# powersensor.net
KiCad netlist of a schematic drawn in EAGLE
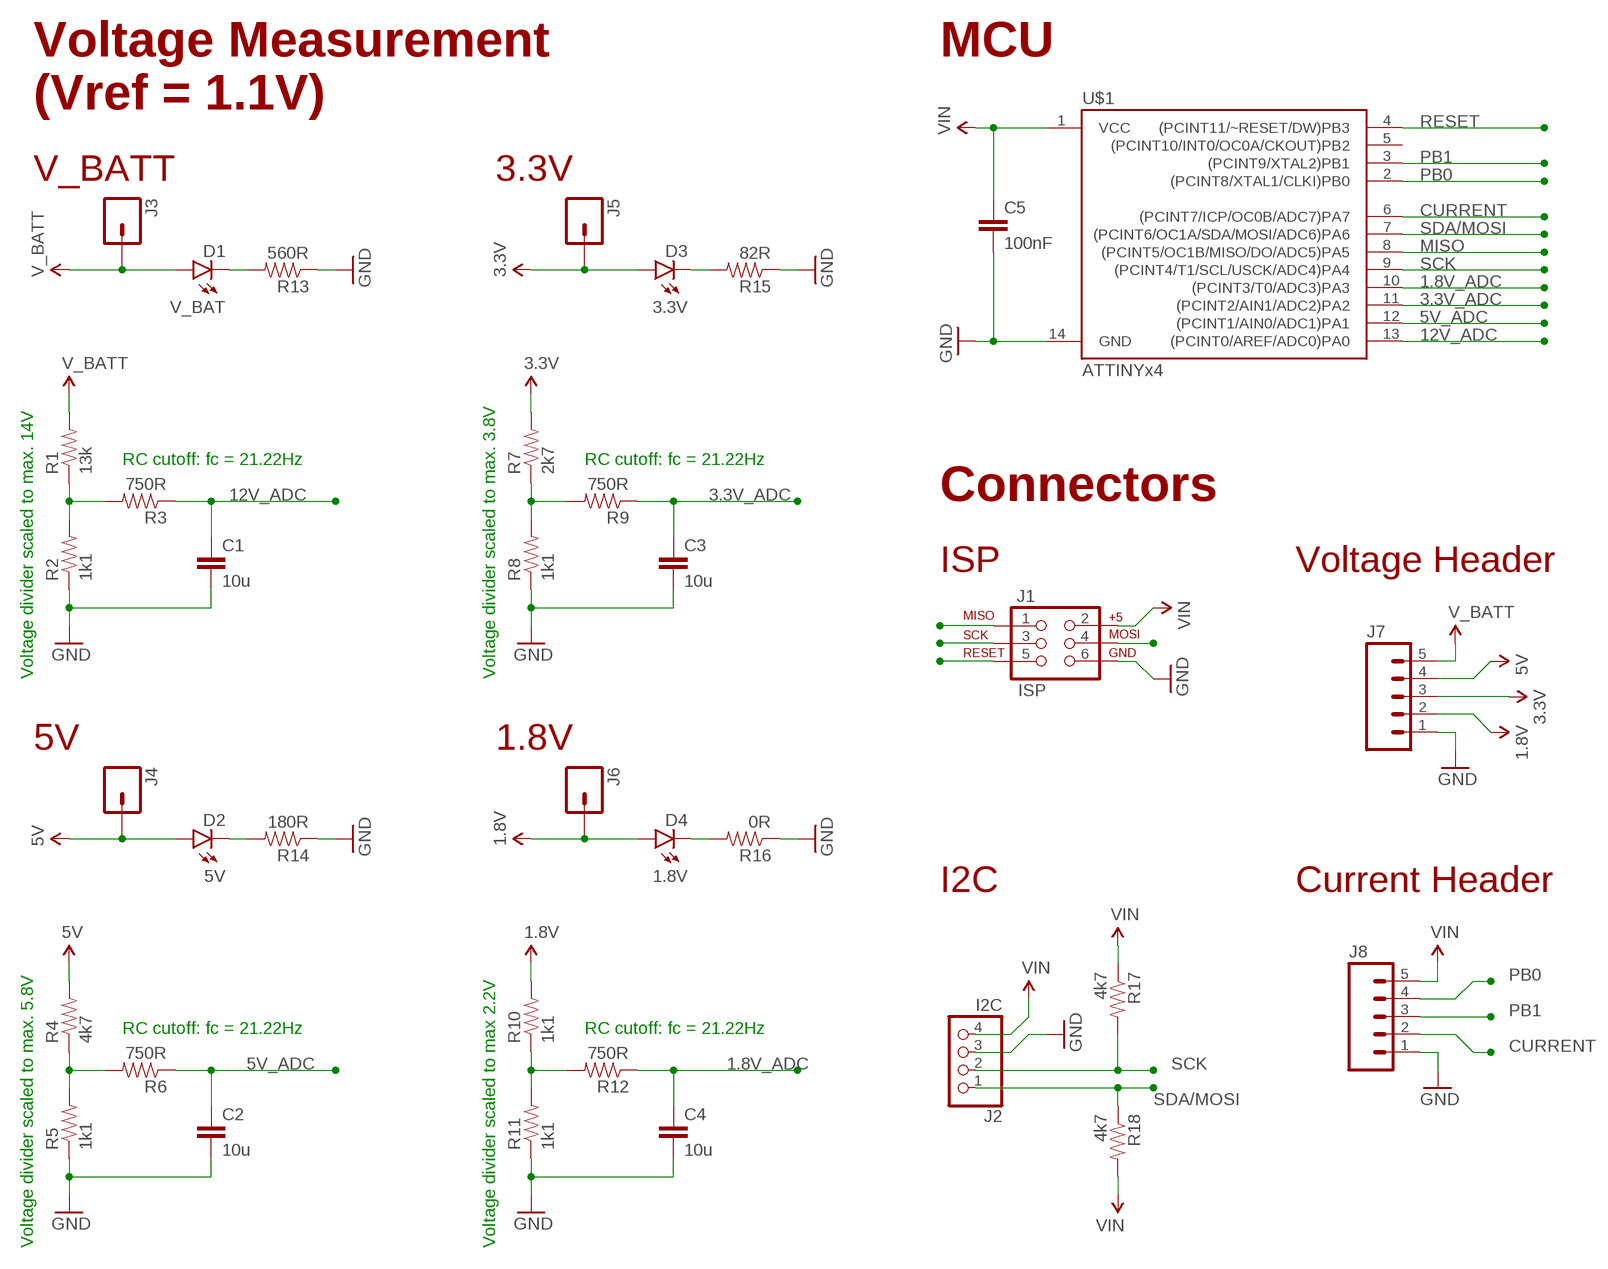
[diagram p0: schematic, sheet 1]

(export (version "E")
  (design (tool "Eeschema 10.0.6"))
  (components
    (comp (ref "C1")
      (value "10u")
      (footprint "eagle-import:0603-CAP")
      (libsource (lib "eagle-import") (part "CAP0603-CAP"))
    )
    (comp (ref "C2")
      (value "10u")
      (footprint "eagle-import:0603-CAP")
      (libsource (lib "eagle-import") (part "CAP0603-CAP"))
    )
    (comp (ref "C3")
      (value "10u")
      (footprint "eagle-import:0603-CAP")
      (libsource (lib "eagle-import") (part "CAP0603-CAP"))
    )
    (comp (ref "C4")
      (value "10u")
      (footprint "eagle-import:0603-CAP")
      (libsource (lib "eagle-import") (part "CAP0603-CAP"))
    )
    (comp (ref "C5")
      (value "100nF")
      (footprint "eagle-import:0603-CAP")
      (libsource (lib "eagle-import") (part "CAP0603-CAP"))
    )
    (comp (ref "D1")
      (value "V_BAT")
      (footprint "eagle-import:LED-0603")
      (libsource (lib "eagle-import") (part "LED0603"))
    )
    (comp (ref "D2")
      (value "5V")
      (footprint "eagle-import:LED-0603")
      (libsource (lib "eagle-import") (part "LED0603"))
    )
    (comp (ref "D3")
      (value "3.3V")
      (footprint "eagle-import:LED-0603")
      (libsource (lib "eagle-import") (part "LED0603"))
    )
    (comp (ref "D4")
      (value "1.8V")
      (footprint "eagle-import:LED-0603")
      (libsource (lib "eagle-import") (part "LED0603"))
    )
    (comp (ref "J1")
      (value "ISP")
      (footprint "eagle-import:2X3")
      (libsource (lib "eagle-import") (part "AVR_SPI_PRG_6PTH"))
    )
    (comp (ref "J2")
      (value "I2C")
      (footprint "eagle-import:1X04_90")
      (libsource (lib "eagle-import") (part "PINHD-1X4/90"))
    )
    (comp (ref "J3")
      (value "M01PTH")
      (footprint "eagle-import:1X01")
      (libsource (lib "eagle-import") (part "M01PTH"))
    )
    (comp (ref "J4")
      (value "M01PTH")
      (footprint "eagle-import:1X01")
      (libsource (lib "eagle-import") (part "M01PTH"))
    )
    (comp (ref "J5")
      (value "M01PTH")
      (footprint "eagle-import:1X01")
      (libsource (lib "eagle-import") (part "M01PTH"))
    )
    (comp (ref "J6")
      (value "M01PTH")
      (footprint "eagle-import:1X01")
      (libsource (lib "eagle-import") (part "M01PTH"))
    )
    (comp (ref "J7")
      (value "M05PTH")
      (footprint "eagle-import:1X05")
      (libsource (lib "eagle-import") (part "M05PTH"))
    )
    (comp (ref "J8")
      (value "M05PTH")
      (footprint "eagle-import:1X05")
      (libsource (lib "eagle-import") (part "M05PTH"))
    )
    (comp (ref "R1")
      (value "13k")
      (footprint "eagle-import:0603-RES")
      (libsource (lib "eagle-import") (part "RESISTOR0603-RES"))
    )
    (comp (ref "R2")
      (value "1k1")
      (footprint "eagle-import:0603-RES")
      (libsource (lib "eagle-import") (part "RESISTOR0603-RES"))
    )
    (comp (ref "R3")
      (value "750R")
      (footprint "eagle-import:0603-RES")
      (libsource (lib "eagle-import") (part "RESISTOR0603-RES"))
    )
    (comp (ref "R4")
      (value "4k7")
      (footprint "eagle-import:0603-RES")
      (libsource (lib "eagle-import") (part "RESISTOR0603-RES"))
    )
    (comp (ref "R5")
      (value "1k1")
      (footprint "eagle-import:0603-RES")
      (libsource (lib "eagle-import") (part "RESISTOR0603-RES"))
    )
    (comp (ref "R6")
      (value "750R")
      (footprint "eagle-import:0603-RES")
      (libsource (lib "eagle-import") (part "RESISTOR0603-RES"))
    )
    (comp (ref "R7")
      (value "2k7")
      (footprint "eagle-import:0603-RES")
      (libsource (lib "eagle-import") (part "RESISTOR0603-RES"))
    )
    (comp (ref "R8")
      (value "1k1")
      (footprint "eagle-import:0603-RES")
      (libsource (lib "eagle-import") (part "RESISTOR0603-RES"))
    )
    (comp (ref "R9")
      (value "750R")
      (footprint "eagle-import:0603-RES")
      (libsource (lib "eagle-import") (part "RESISTOR0603-RES"))
    )
    (comp (ref "R10")
      (value "1k1")
      (footprint "eagle-import:0603-RES")
      (libsource (lib "eagle-import") (part "RESISTOR0603-RES"))
    )
    (comp (ref "R11")
      (value "1k1")
      (footprint "eagle-import:0603-RES")
      (libsource (lib "eagle-import") (part "RESISTOR0603-RES"))
    )
    (comp (ref "R12")
      (value "750R")
      (footprint "eagle-import:0603-RES")
      (libsource (lib "eagle-import") (part "RESISTOR0603-RES"))
    )
    (comp (ref "R13")
      (value "560R")
      (footprint "eagle-import:0603-RES")
      (libsource (lib "eagle-import") (part "RESISTOR0603-RES"))
    )
    (comp (ref "R14")
      (value "180R")
      (footprint "eagle-import:0603-RES")
      (libsource (lib "eagle-import") (part "RESISTOR0603-RES"))
    )
    (comp (ref "R15")
      (value "82R")
      (footprint "eagle-import:0603-RES")
      (libsource (lib "eagle-import") (part "RESISTOR0603-RES"))
    )
    (comp (ref "R16")
      (value "0R")
      (footprint "eagle-import:0603-RES")
      (libsource (lib "eagle-import") (part "RESISTOR0603-RES"))
    )
    (comp (ref "R17")
      (value "4k7")
      (footprint "eagle-import:0603-RES")
      (libsource (lib "eagle-import") (part "RESISTOR0603-RES"))
    )
    (comp (ref "R18")
      (value "4k7")
      (footprint "eagle-import:0603-RES")
      (libsource (lib "eagle-import") (part "RESISTOR0603-RES"))
    )
    (comp (ref "U$1")
      (value "ATTINYx4")
      (footprint "eagle-import:SO14")
      (libsource (lib "eagle-import") (part "ATTINY84"))
    )
  )
  (nets
    (net (code "1") (name "/1.8V_ADC") (class "Default")
      (node (ref "C4") (pin "1") (pinfunction "1_1") (pintype "passive"))
      (node (ref "R12") (pin "1") (pinfunction "1_1") (pintype "passive"))
      (node (ref "U$1") (pin "10") (pinfunction "(PCINT3/T0/ADC3)PA3_10") (pintype "bidirectional"))
    )
    (net (code "2") (name "/3.3V_ADC") (class "Default")
      (node (ref "C3") (pin "1") (pinfunction "1_1") (pintype "passive"))
      (node (ref "R9") (pin "1") (pinfunction "1_1") (pintype "passive"))
      (node (ref "U$1") (pin "11") (pinfunction "(PCINT2/AIN1/ADC2)PA2_11") (pintype "bidirectional"))
    )
    (net (code "3") (name "/5V_ADC") (class "Default")
      (node (ref "C2") (pin "1") (pinfunction "1_1") (pintype "passive"))
      (node (ref "R6") (pin "1") (pinfunction "1_1") (pintype "passive"))
      (node (ref "U$1") (pin "12") (pinfunction "(PCINT1/AIN0/ADC1)PA1_12") (pintype "bidirectional"))
    )
    (net (code "4") (name "/12V_ADC") (class "Default")
      (node (ref "C1") (pin "1") (pinfunction "1_1") (pintype "passive"))
      (node (ref "R3") (pin "1") (pinfunction "1_1") (pintype "passive"))
      (node (ref "U$1") (pin "13") (pinfunction "(PCINT0/AREF/ADC0)PA0_13") (pintype "bidirectional"))
    )
    (net (code "5") (name "/CURRENT") (class "Default")
      (node (ref "J8") (pin "2") (pinfunction "2_2") (pintype "passive"))
      (node (ref "U$1") (pin "6") (pinfunction "(PCINT7/ICP/OC0B/ADC7)PA7_6") (pintype "bidirectional"))
    )
    (net (code "6") (name "/MISO") (class "Default")
      (node (ref "J1") (pin "1") (pinfunction "1_1") (pintype "passive"))
      (node (ref "U$1") (pin "8") (pinfunction "(PCINT5/OC1B/MISO/DO/ADC5)PA5_8") (pintype "bidirectional"))
    )
    (net (code "7") (name "/PB0") (class "Default")
      (node (ref "J8") (pin "4") (pinfunction "4_4") (pintype "passive"))
      (node (ref "U$1") (pin "2") (pinfunction "(PCINT8/XTAL1/CLKI)PB0_2") (pintype "bidirectional"))
    )
    (net (code "8") (name "/PB1") (class "Default")
      (node (ref "J8") (pin "3") (pinfunction "3_3") (pintype "passive"))
      (node (ref "U$1") (pin "3") (pinfunction "(PCINT9/XTAL2)PB1_3") (pintype "bidirectional"))
    )
    (net (code "9") (name "/RESET") (class "Default")
      (node (ref "J1") (pin "5") (pinfunction "5_5") (pintype "passive"))
      (node (ref "U$1") (pin "4") (pinfunction "(PCINT11/~{RESET/DW})PB3_4") (pintype "bidirectional"))
    )
    (net (code "10") (name "/SCK") (class "Default")
      (node (ref "J1") (pin "3") (pinfunction "3_3") (pintype "passive"))
      (node (ref "J2") (pin "2") (pinfunction "2_2") (pintype "passive"))
      (node (ref "R17") (pin "2") (pinfunction "2_2") (pintype "passive"))
      (node (ref "U$1") (pin "9") (pinfunction "(PCINT4/T1/SCL/USCK/ADC4)PA4_9") (pintype "bidirectional"))
    )
    (net (code "11") (name "/SDA{slash}MOSI") (class "Default")
      (node (ref "J1") (pin "4") (pinfunction "4_4") (pintype "passive"))
      (node (ref "J2") (pin "1") (pinfunction "1_1") (pintype "passive"))
      (node (ref "R18") (pin "1") (pinfunction "1_1") (pintype "passive"))
      (node (ref "U$1") (pin "7") (pinfunction "(PCINT6/OC1A/SDA/MOSI/ADC6)PA6_7") (pintype "bidirectional"))
    )
    (net (code "12") (name "1.8V") (class "Default")
      (node (ref "D4") (pin "A") (pinfunction "A_A") (pintype "passive"))
      (node (ref "J6") (pin "1") (pinfunction "1_1") (pintype "passive"))
      (node (ref "J7") (pin "2") (pinfunction "2_2") (pintype "passive"))
      (node (ref "R10") (pin "2") (pinfunction "2_2") (pintype "passive"))
    )
    (net (code "13") (name "3.3V") (class "Default")
      (node (ref "D3") (pin "A") (pinfunction "A_A") (pintype "passive"))
      (node (ref "J5") (pin "1") (pinfunction "1_1") (pintype "passive"))
      (node (ref "J7") (pin "3") (pinfunction "3_3") (pintype "passive"))
      (node (ref "R7") (pin "2") (pinfunction "2_2") (pintype "passive"))
    )
    (net (code "14") (name "5V") (class "Default")
      (node (ref "D2") (pin "A") (pinfunction "A_A") (pintype "passive"))
      (node (ref "J4") (pin "1") (pinfunction "1_1") (pintype "passive"))
      (node (ref "J7") (pin "4") (pinfunction "4_4") (pintype "passive"))
      (node (ref "R4") (pin "2") (pinfunction "2_2") (pintype "passive"))
    )
    (net (code "15") (name "GND") (class "Default")
      (node (ref "C1") (pin "2") (pinfunction "2_2") (pintype "passive"))
      (node (ref "C2") (pin "2") (pinfunction "2_2") (pintype "passive"))
      (node (ref "C3") (pin "2") (pinfunction "2_2") (pintype "passive"))
      (node (ref "C4") (pin "2") (pinfunction "2_2") (pintype "passive"))
      (node (ref "C5") (pin "2") (pinfunction "2_2") (pintype "passive"))
      (node (ref "J1") (pin "6") (pinfunction "6_6") (pintype "passive"))
      (node (ref "J2") (pin "3") (pinfunction "3_3") (pintype "passive"))
      (node (ref "J7") (pin "1") (pinfunction "1_1") (pintype "passive"))
      (node (ref "J8") (pin "1") (pinfunction "1_1") (pintype "passive"))
      (node (ref "R11") (pin "1") (pinfunction "1_1") (pintype "passive"))
      (node (ref "R13") (pin "1") (pinfunction "1_1") (pintype "passive"))
      (node (ref "R14") (pin "1") (pinfunction "1_1") (pintype "passive"))
      (node (ref "R15") (pin "1") (pinfunction "1_1") (pintype "passive"))
      (node (ref "R16") (pin "1") (pinfunction "1_1") (pintype "passive"))
      (node (ref "R2") (pin "1") (pinfunction "1_1") (pintype "passive"))
      (node (ref "R5") (pin "1") (pinfunction "1_1") (pintype "passive"))
      (node (ref "R8") (pin "1") (pinfunction "1_1") (pintype "passive"))
      (node (ref "U$1") (pin "14") (pinfunction "GND_14") (pintype "bidirectional"))
    )
    (net (code "16") (name "Net-(D1-PadC)") (class "Default")
      (node (ref "D1") (pin "C") (pinfunction "C_C") (pintype "passive"))
      (node (ref "R13") (pin "2") (pinfunction "2_2") (pintype "passive"))
    )
    (net (code "17") (name "Net-(D2-PadC)") (class "Default")
      (node (ref "D2") (pin "C") (pinfunction "C_C") (pintype "passive"))
      (node (ref "R14") (pin "2") (pinfunction "2_2") (pintype "passive"))
    )
    (net (code "18") (name "Net-(D3-PadC)") (class "Default")
      (node (ref "D3") (pin "C") (pinfunction "C_C") (pintype "passive"))
      (node (ref "R15") (pin "2") (pinfunction "2_2") (pintype "passive"))
    )
    (net (code "19") (name "Net-(D4-PadC)") (class "Default")
      (node (ref "D4") (pin "C") (pinfunction "C_C") (pintype "passive"))
      (node (ref "R16") (pin "2") (pinfunction "2_2") (pintype "passive"))
    )
    (net (code "20") (name "Net-(R1-Pad1)") (class "Default")
      (node (ref "R1") (pin "1") (pinfunction "1_1") (pintype "passive"))
      (node (ref "R2") (pin "2") (pinfunction "2_2") (pintype "passive"))
      (node (ref "R3") (pin "2") (pinfunction "2_2") (pintype "passive"))
    )
    (net (code "21") (name "Net-(R4-Pad1)") (class "Default")
      (node (ref "R4") (pin "1") (pinfunction "1_1") (pintype "passive"))
      (node (ref "R5") (pin "2") (pinfunction "2_2") (pintype "passive"))
      (node (ref "R6") (pin "2") (pinfunction "2_2") (pintype "passive"))
    )
    (net (code "22") (name "Net-(R7-Pad1)") (class "Default")
      (node (ref "R7") (pin "1") (pinfunction "1_1") (pintype "passive"))
      (node (ref "R8") (pin "2") (pinfunction "2_2") (pintype "passive"))
      (node (ref "R9") (pin "2") (pinfunction "2_2") (pintype "passive"))
    )
    (net (code "23") (name "Net-(R10-Pad1)") (class "Default")
      (node (ref "R10") (pin "1") (pinfunction "1_1") (pintype "passive"))
      (node (ref "R11") (pin "2") (pinfunction "2_2") (pintype "passive"))
      (node (ref "R12") (pin "2") (pinfunction "2_2") (pintype "passive"))
    )
    (net (code "24") (name "VIN") (class "Default")
      (node (ref "C5") (pin "1") (pinfunction "1_1") (pintype "passive"))
      (node (ref "J1") (pin "2") (pinfunction "2_2") (pintype "passive"))
      (node (ref "J2") (pin "4") (pinfunction "4_4") (pintype "passive"))
      (node (ref "J8") (pin "5") (pinfunction "5_5") (pintype "passive"))
      (node (ref "R17") (pin "1") (pinfunction "1_1") (pintype "passive"))
      (node (ref "R18") (pin "2") (pinfunction "2_2") (pintype "passive"))
      (node (ref "U$1") (pin "1") (pinfunction "VCC_1") (pintype "bidirectional"))
    )
    (net (code "25") (name "V_BATT") (class "Default")
      (node (ref "D1") (pin "A") (pinfunction "A_A") (pintype "passive"))
      (node (ref "J3") (pin "1") (pinfunction "1_1") (pintype "passive"))
      (node (ref "J7") (pin "5") (pinfunction "5_5") (pintype "passive"))
      (node (ref "R1") (pin "2") (pinfunction "2_2") (pintype "passive"))
    )
    (net (code "26") (name "unconnected-(U$1-(PCINT10{slash}INT0{slash}OC0A{slash}CKOUT)PB2-Pad5)") (class "Default")
      (node (ref "U$1") (pin "5") (pinfunction "(PCINT10/INT0/OC0A/CKOUT)PB2_5") (pintype "bidirectional"))
    )
  )
)
